# Simple-LM358-OP-AMP-based-USB-Li-ion-cha.net
KiCad netlist of a schematic drawn in EAGLE
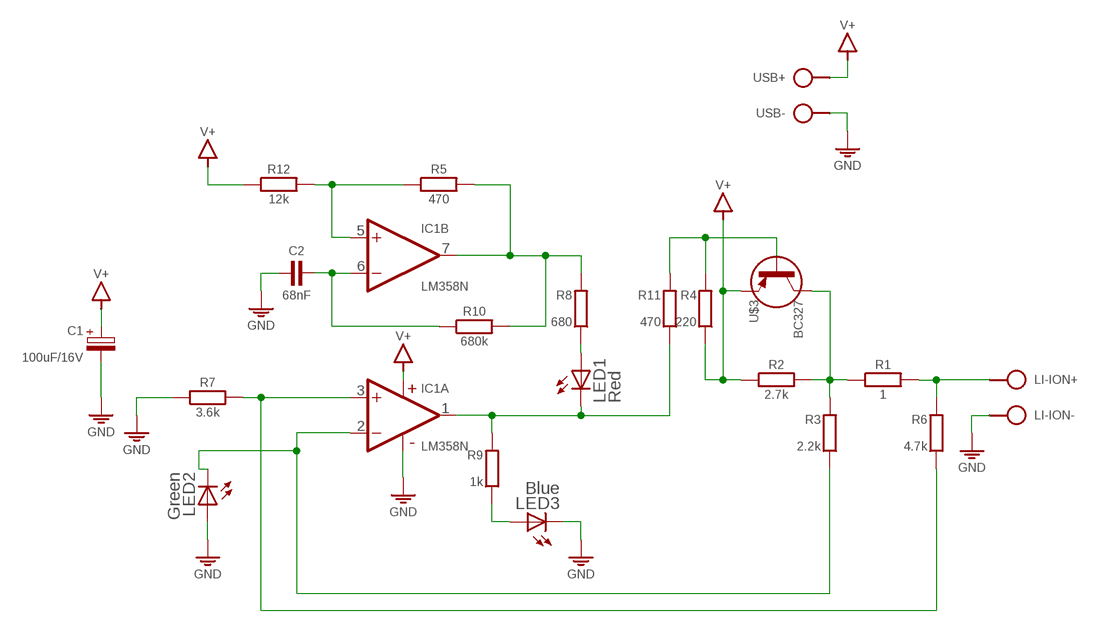
[diagram p0: schematic, sheet 1]

(export (version "E")
  (design (tool "Eeschema 10.0.6"))
  (components
    (comp (ref "C1")
      (value "100uF/16V")
      (footprint "eagle-import:E2,5-5")
      (libsource (lib "eagle-import") (part "CPOLE2.5-5"))
    )
    (comp (ref "C2")
      (value "68nF")
      (footprint "eagle-import:C050-020X044")
      (libsource (lib "eagle-import") (part "C-H050-020X044"))
    )
    (comp (ref "IC1")
      (value "LM358N")
      (footprint "eagle-import:DIL08")
      (libsource (lib "eagle-import") (part "LM358N"))
    )
    (comp (ref "LED1")
      (value "Red")
      (footprint "eagle-import:LED3MM")
      (libsource (lib "eagle-import") (part "LED3MM"))
    )
    (comp (ref "LED2")
      (value "Green")
      (footprint "eagle-import:LED3MM")
      (libsource (lib "eagle-import") (part "LED3MM"))
    )
    (comp (ref "LED3")
      (value "Blue")
      (footprint "eagle-import:LED3MM")
      (libsource (lib "eagle-import") (part "LED3MM"))
    )
    (comp (ref "LI-ION")
      (value "SPAD+-+-")
      (footprint "eagle-import:SPAD+-")
      (libsource (lib "eagle-import") (part "SPAD+-+-"))
    )
    (comp (ref "R1")
      (value "1")
      (footprint "eagle-import:0204_10")
      (libsource (lib "eagle-import") (part "R-H0204/10"))
    )
    (comp (ref "R2")
      (value "2.7k")
      (footprint "eagle-import:0204_10-V")
      (libsource (lib "eagle-import") (part "R-H0204/10-V"))
    )
    (comp (ref "R3")
      (value "2.2k")
      (footprint "eagle-import:0204_10-V")
      (libsource (lib "eagle-import") (part "R0204/10-V"))
    )
    (comp (ref "R4")
      (value "220")
      (footprint "eagle-import:0204_10-V")
      (libsource (lib "eagle-import") (part "R0204/10-V"))
    )
    (comp (ref "R5")
      (value "470")
      (footprint "eagle-import:0204_7-V")
      (libsource (lib "eagle-import") (part "R-H0204/7-V"))
    )
    (comp (ref "R6")
      (value "4.7k")
      (footprint "eagle-import:0204_10-V")
      (libsource (lib "eagle-import") (part "R0204/10-V"))
    )
    (comp (ref "R7")
      (value "3.6k")
      (footprint "eagle-import:0204_10")
      (libsource (lib "eagle-import") (part "R-H0204/10"))
    )
    (comp (ref "R8")
      (value "680")
      (footprint "eagle-import:0204_10-V")
      (libsource (lib "eagle-import") (part "R0204/10-V"))
    )
    (comp (ref "R9")
      (value "1k")
      (footprint "eagle-import:0204_10")
      (libsource (lib "eagle-import") (part "R0204/10"))
    )
    (comp (ref "R10")
      (value "680k")
      (footprint "eagle-import:0204_10-V")
      (libsource (lib "eagle-import") (part "R-H0204/10-V"))
    )
    (comp (ref "R11")
      (value "470")
      (footprint "eagle-import:0204_10-V")
      (libsource (lib "eagle-import") (part "R0204/10-V"))
    )
    (comp (ref "R12")
      (value "12k")
      (footprint "eagle-import:0204_10-V")
      (libsource (lib "eagle-import") (part "R-H0204/10-V"))
    )
    (comp (ref "U$3")
      (value "BC327")
      (footprint "eagle-import:TO92")
      (libsource (lib "eagle-import") (part "BC327"))
    )
    (comp (ref "USB")
      (value "SPAD+--+")
      (footprint "eagle-import:SPAD-+")
      (libsource (lib "eagle-import") (part "SPAD+--+"))
    )
  )
  (nets
    (net (code "1") (name "GND") (class "Default")
      (node (ref "C1") (pin "-") (pinfunction "-_-") (pintype "passive"))
      (node (ref "C2") (pin "1") (pinfunction "1_1") (pintype "passive"))
      (node (ref "IC1") (pin "4") (pinfunction "V-_4") (pintype "power_in"))
      (node (ref "LED2") (pin "A") (pinfunction "A_A") (pintype "passive"))
      (node (ref "LED3") (pin "K") (pinfunction "C_K") (pintype "passive"))
      (node (ref "LI-ION") (pin "1") (pinfunction "P$1_1") (pintype "passive"))
      (node (ref "R7") (pin "1") (pinfunction "1_1") (pintype "passive"))
      (node (ref "USB") (pin "1") (pinfunction "P$1_1") (pintype "passive"))
    )
    (net (code "2") (name "Net-(IC1A-+IN)") (class "Default")
      (node (ref "IC1") (pin "3") (pinfunction "+IN_3") (pintype "input"))
      (node (ref "R6") (pin "2") (pinfunction "2_2") (pintype "passive"))
      (node (ref "R7") (pin "2") (pinfunction "2_2") (pintype "passive"))
    )
    (net (code "3") (name "Net-(IC1A--IN)") (class "Default")
      (node (ref "IC1") (pin "2") (pinfunction "-IN_2") (pintype "input"))
      (node (ref "LED2") (pin "K") (pinfunction "C_K") (pintype "passive"))
      (node (ref "R3") (pin "2") (pinfunction "2_2") (pintype "passive"))
    )
    (net (code "4") (name "Net-(IC1A-OUT)") (class "Default")
      (node (ref "IC1") (pin "1") (pinfunction "OUT_1") (pintype "output"))
      (node (ref "LED1") (pin "K") (pinfunction "C_K") (pintype "passive"))
      (node (ref "R11") (pin "2") (pinfunction "2_2") (pintype "passive"))
      (node (ref "R9") (pin "2") (pinfunction "1_2") (pintype "passive"))
    )
    (net (code "5") (name "Net-(IC1B-+IN)") (class "Default")
      (node (ref "IC1") (pin "5") (pinfunction "+IN_5") (pintype "input"))
      (node (ref "R12") (pin "2") (pinfunction "2_2") (pintype "passive"))
      (node (ref "R5") (pin "1") (pinfunction "1_1") (pintype "passive"))
    )
    (net (code "6") (name "Net-(IC1B--IN)") (class "Default")
      (node (ref "C2") (pin "2") (pinfunction "2_2") (pintype "passive"))
      (node (ref "IC1") (pin "6") (pinfunction "-IN_6") (pintype "input"))
      (node (ref "R10") (pin "1") (pinfunction "1_1") (pintype "passive"))
    )
    (net (code "7") (name "Net-(IC1B-OUT)") (class "Default")
      (node (ref "IC1") (pin "7") (pinfunction "OUT_7") (pintype "output"))
      (node (ref "R10") (pin "2") (pinfunction "2_2") (pintype "passive"))
      (node (ref "R5") (pin "2") (pinfunction "2_2") (pintype "passive"))
      (node (ref "R8") (pin "1") (pinfunction "1_1") (pintype "passive"))
    )
    (net (code "8") (name "Net-(LED1-PadA)") (class "Default")
      (node (ref "LED1") (pin "A") (pinfunction "A_A") (pintype "passive"))
      (node (ref "R8") (pin "2") (pinfunction "2_2") (pintype "passive"))
    )
    (net (code "9") (name "Net-(LI-IONA-P$1)") (class "Default")
      (node (ref "LI-ION") (pin "2") (pinfunction "P$1_2") (pintype "passive"))
      (node (ref "R1") (pin "2") (pinfunction "2_2") (pintype "passive"))
      (node (ref "R6") (pin "1") (pinfunction "1_1") (pintype "passive"))
    )
    (net (code "10") (name "Net-(R9-2)") (class "Default")
      (node (ref "LED3") (pin "A") (pinfunction "A_A") (pintype "passive"))
      (node (ref "R9") (pin "1") (pinfunction "2_1") (pintype "passive"))
    )
    (net (code "11") (name "Net-(U$3-B)") (class "Default")
      (node (ref "R11") (pin "1") (pinfunction "1_1") (pintype "passive"))
      (node (ref "R4") (pin "1") (pinfunction "1_1") (pintype "passive"))
      (node (ref "U$3") (pin "2") (pinfunction "B_2") (pintype "passive"))
    )
    (net (code "12") (name "Net-(U$3-C)") (class "Default")
      (node (ref "R1") (pin "1") (pinfunction "1_1") (pintype "passive"))
      (node (ref "R2") (pin "2") (pinfunction "2_2") (pintype "passive"))
      (node (ref "R3") (pin "1") (pinfunction "1_1") (pintype "passive"))
      (node (ref "U$3") (pin "1") (pinfunction "C_1") (pintype "passive"))
    )
    (net (code "13") (name "V+") (class "Default")
      (node (ref "C1") (pin "+") (pinfunction "+_+") (pintype "passive"))
      (node (ref "IC1") (pin "8") (pinfunction "V+_8") (pintype "power_in"))
      (node (ref "R12") (pin "1") (pinfunction "1_1") (pintype "passive"))
      (node (ref "R2") (pin "1") (pinfunction "1_1") (pintype "passive"))
      (node (ref "R4") (pin "2") (pinfunction "2_2") (pintype "passive"))
      (node (ref "U$3") (pin "3") (pinfunction "E_3") (pintype "passive"))
      (node (ref "USB") (pin "2") (pinfunction "P$1_2") (pintype "passive"))
    )
  )
)
